# SlaveV2.net
KiCad netlist of a schematic drawn in EAGLE
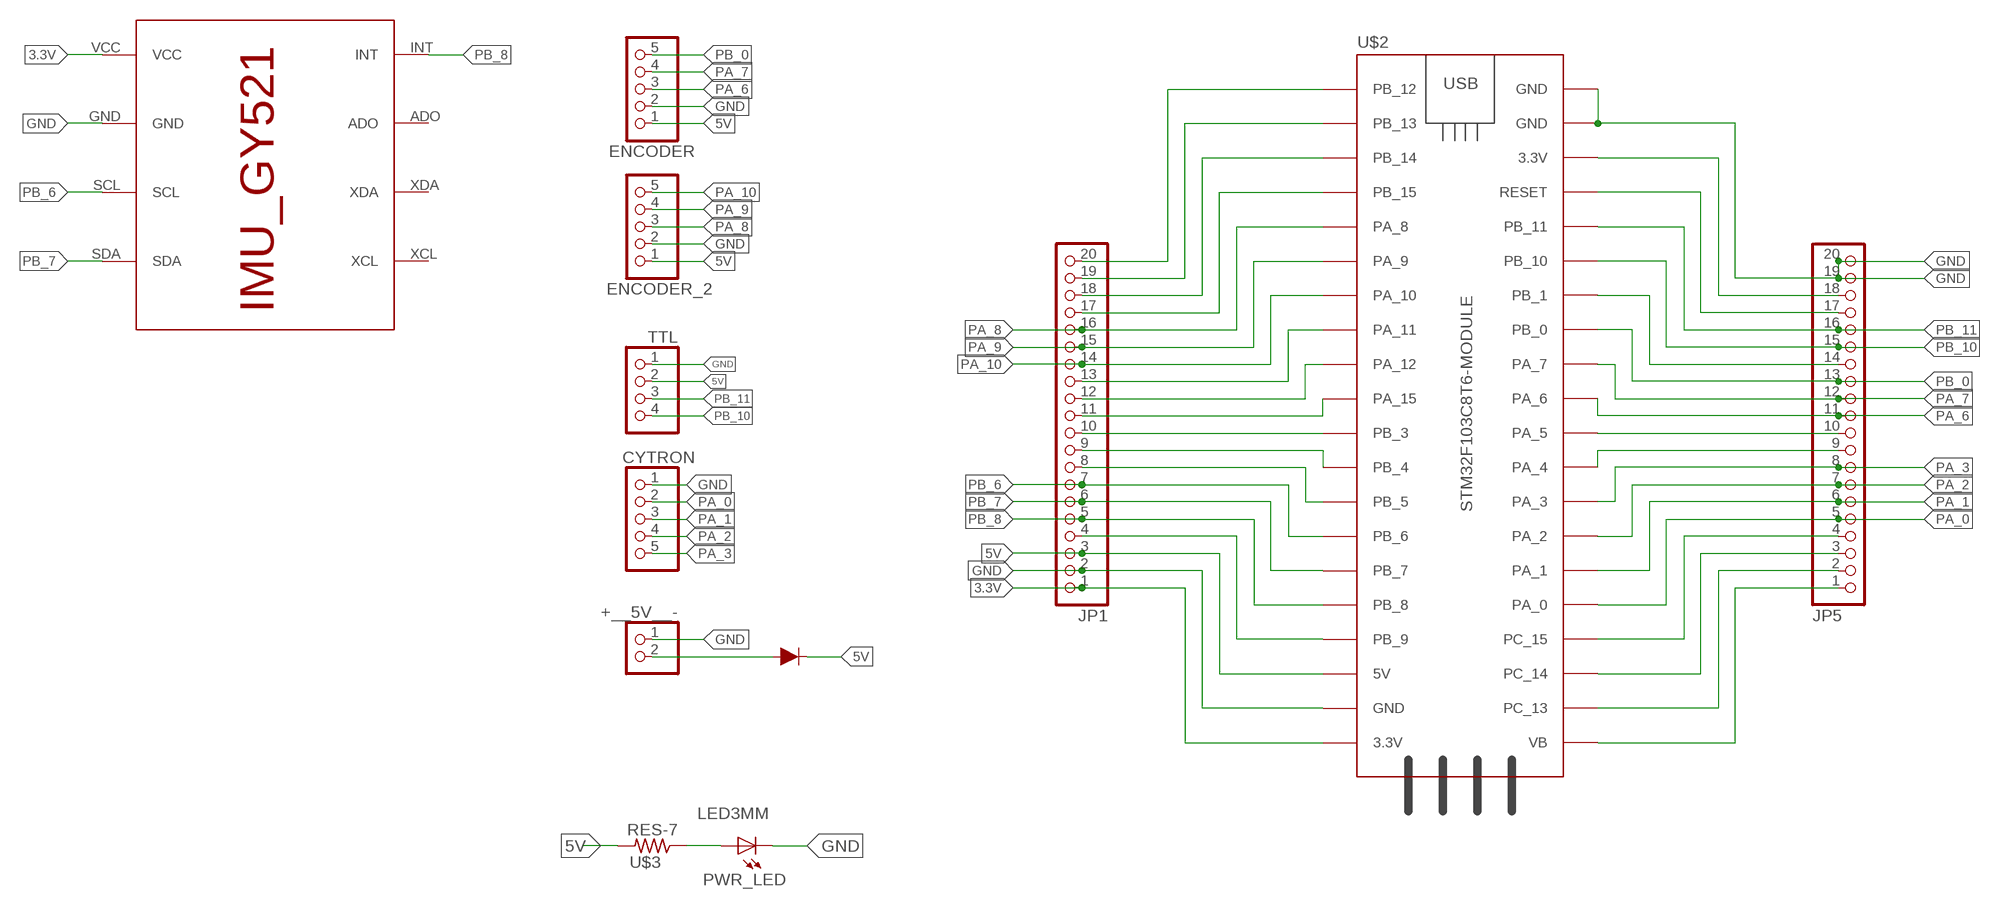
[diagram p0: schematic, sheet 1]

(export (version "E")
  (design (tool "Eeschema 10.0.6"))
  (components
    (comp (ref "+__5V__-")
      (value "PINHD-2_DATA")
      (footprint "eagle-import:1X02_DATA")
      (libsource (lib "eagle-import") (part "PINHD-2_DATA"))
    )
    (comp (ref "CYTRON")
      (value "PINHD-5_DATA")
      (footprint "eagle-import:1X05_DATA")
      (libsource (lib "eagle-import") (part "PINHD-5_DATA"))
    )
    (comp (ref "D1")
      (value "200mA/100V/1V")
      (footprint "eagle-import:DIODE-1N4148")
      (libsource (lib "eagle-import") (part "DIODE(1A)-1N4148"))
    )
    (comp (ref "ENCODER")
      (value "PINHD-5_DATA")
      (footprint "eagle-import:1X05_DATA")
      (libsource (lib "eagle-import") (part "PINHD-5_DATA"))
    )
    (comp (ref "ENCODER_2")
      (value "PINHD-5_DATA")
      (footprint "eagle-import:1X05_DATA")
      (libsource (lib "eagle-import") (part "PINHD-5_DATA"))
    )
    (comp (ref "IMU")
      (value "IMU_ROBOCON_GY521")
      (footprint "eagle-import:IMU_GY521")
      (libsource (lib "eagle-import") (part "IMU_ROBOCON_GY521"))
    )
    (comp (ref "JP1")
      (value "PINHD-1X20")
      (footprint "eagle-import:1X20")
      (libsource (lib "eagle-import") (part "PINHD-1X20"))
    )
    (comp (ref "JP5")
      (value "PINHD-1X20")
      (footprint "eagle-import:1X20")
      (libsource (lib "eagle-import") (part "PINHD-1X20"))
    )
    (comp (ref "PWR_LED")
      (value "LED3MM")
      (footprint "eagle-import:LED3MM")
      (libsource (lib "eagle-import") (part "LED3MM"))
    )
    (comp (ref "TTL")
      (value "PINHD-4_DATA")
      (footprint "eagle-import:1X04_DATA")
      (libsource (lib "eagle-import") (part "PINHD-4_DATA"))
    )
    (comp (ref "U$2")
      (value "STM32F103C8T6-MODULE")
      (footprint "eagle-import:STM32F103C8T6-MODULE")
      (libsource (lib "eagle-import") (part "STM32F103C8T6-MODULE"))
    )
    (comp (ref "U$3")
      (value "RES-7")
      (footprint "eagle-import:0204_7")
      (libsource (lib "eagle-import") (part "RES-7"))
    )
  )
  (nets
    (net (code "1") (name "3.3V") (class "Default")
      (node (ref "IMU") (pin "VCC") (pinfunction "VCC_VCC") (pintype "bidirectional"))
      (node (ref "JP1") (pin "1") (pinfunction "1_1") (pintype "passive"))
      (node (ref "U$2") (pin "3.3V_1") (pinfunction "3.3V_3.3V_1") (pintype "bidirectional"))
    )
    (net (code "2") (name "5V") (class "Default")
      (node (ref "D1") (pin "C") (pinfunction "C_C") (pintype "passive"))
      (node (ref "ENCODER") (pin "1") (pinfunction "1_1") (pintype "passive"))
      (node (ref "ENCODER_2") (pin "1") (pinfunction "1_1") (pintype "passive"))
      (node (ref "JP1") (pin "3") (pinfunction "3_3") (pintype "passive"))
      (node (ref "TTL") (pin "2") (pinfunction "2_2") (pintype "passive"))
      (node (ref "U$2") (pin "5V") (pinfunction "5V_5V") (pintype "bidirectional"))
      (node (ref "U$3") (pin "2") (pinfunction "2_2") (pintype "passive"))
    )
    (net (code "3") (name "GND") (class "Default")
      (node (ref "+__5V__-") (pin "1") (pinfunction "1_1") (pintype "passive"))
      (node (ref "CYTRON") (pin "1") (pinfunction "1_1") (pintype "passive"))
      (node (ref "ENCODER") (pin "2") (pinfunction "2_2") (pintype "passive"))
      (node (ref "ENCODER_2") (pin "2") (pinfunction "2_2") (pintype "passive"))
      (node (ref "IMU") (pin "GND") (pinfunction "GND_GND") (pintype "bidirectional"))
      (node (ref "JP1") (pin "2") (pinfunction "2_2") (pintype "passive"))
      (node (ref "JP5") (pin "19") (pinfunction "19_19") (pintype "passive"))
      (node (ref "JP5") (pin "20") (pinfunction "20_20") (pintype "passive"))
      (node (ref "PWR_LED") (pin "K") (pinfunction "C_K") (pintype "passive"))
      (node (ref "TTL") (pin "1") (pinfunction "1_1") (pintype "passive"))
      (node (ref "U$2") (pin "GND_1") (pinfunction "GND_GND_1") (pintype "bidirectional"))
      (node (ref "U$2") (pin "GND_2") (pinfunction "GND_GND_2") (pintype "bidirectional"))
      (node (ref "U$2") (pin "GND_3") (pinfunction "GND_GND_3") (pintype "power_in"))
    )
    (net (code "4") (name "Net-(+__5V__--Pad2)") (class "Default")
      (node (ref "+__5V__-") (pin "2") (pinfunction "2_2") (pintype "passive"))
      (node (ref "D1") (pin "A") (pinfunction "A_A") (pintype "passive"))
    )
    (net (code "5") (name "Net-(JP1-Pad4)") (class "Default")
      (node (ref "JP1") (pin "4") (pinfunction "4_4") (pintype "passive"))
      (node (ref "U$2") (pin "PB_9") (pinfunction "PB_9_PB_9") (pintype "bidirectional"))
    )
    (net (code "6") (name "Net-(JP1-Pad8)") (class "Default")
      (node (ref "JP1") (pin "8") (pinfunction "8_8") (pintype "passive"))
      (node (ref "U$2") (pin "PB_5") (pinfunction "PB_5_PB_5") (pintype "bidirectional"))
    )
    (net (code "7") (name "Net-(JP1-Pad9)") (class "Default")
      (node (ref "JP1") (pin "9") (pinfunction "9_9") (pintype "passive"))
      (node (ref "U$2") (pin "PB_4") (pinfunction "PB_4_PB_4") (pintype "bidirectional"))
    )
    (net (code "8") (name "Net-(JP1-Pad10)") (class "Default")
      (node (ref "JP1") (pin "10") (pinfunction "10_10") (pintype "passive"))
      (node (ref "U$2") (pin "PB_3") (pinfunction "PB_3_PB_3") (pintype "bidirectional"))
    )
    (net (code "9") (name "Net-(JP1-Pad11)") (class "Default")
      (node (ref "JP1") (pin "11") (pinfunction "11_11") (pintype "passive"))
      (node (ref "U$2") (pin "PA_15") (pinfunction "PA_15_PA_15") (pintype "bidirectional"))
    )
    (net (code "10") (name "Net-(JP1-Pad12)") (class "Default")
      (node (ref "JP1") (pin "12") (pinfunction "12_12") (pintype "passive"))
      (node (ref "U$2") (pin "PA_12") (pinfunction "PA_12_PA_12") (pintype "bidirectional"))
    )
    (net (code "11") (name "Net-(JP1-Pad13)") (class "Default")
      (node (ref "JP1") (pin "13") (pinfunction "13_13") (pintype "passive"))
      (node (ref "U$2") (pin "PA_11") (pinfunction "PA_11_PA_11") (pintype "bidirectional"))
    )
    (net (code "12") (name "Net-(JP1-Pad17)") (class "Default")
      (node (ref "JP1") (pin "17") (pinfunction "17_17") (pintype "passive"))
      (node (ref "U$2") (pin "PB_15") (pinfunction "PB_15_PB_15") (pintype "bidirectional"))
    )
    (net (code "13") (name "Net-(JP1-Pad18)") (class "Default")
      (node (ref "JP1") (pin "18") (pinfunction "18_18") (pintype "passive"))
      (node (ref "U$2") (pin "PB_14") (pinfunction "PB_14_PB_14") (pintype "bidirectional"))
    )
    (net (code "14") (name "Net-(JP1-Pad19)") (class "Default")
      (node (ref "JP1") (pin "19") (pinfunction "19_19") (pintype "passive"))
      (node (ref "U$2") (pin "PB_13") (pinfunction "PB_13_PB_13") (pintype "bidirectional"))
    )
    (net (code "15") (name "Net-(JP1-Pad20)") (class "Default")
      (node (ref "JP1") (pin "20") (pinfunction "20_20") (pintype "passive"))
      (node (ref "U$2") (pin "PB_12") (pinfunction "PB_12_PB_12") (pintype "bidirectional"))
    )
    (net (code "16") (name "Net-(JP5-Pad1)") (class "Default")
      (node (ref "JP5") (pin "1") (pinfunction "1_1") (pintype "passive"))
      (node (ref "U$2") (pin "VB") (pinfunction "VB_VB") (pintype "bidirectional"))
    )
    (net (code "17") (name "Net-(JP5-Pad2)") (class "Default")
      (node (ref "JP5") (pin "2") (pinfunction "2_2") (pintype "passive"))
      (node (ref "U$2") (pin "PC_13") (pinfunction "PC_13_PC_13") (pintype "bidirectional"))
    )
    (net (code "18") (name "Net-(JP5-Pad3)") (class "Default")
      (node (ref "JP5") (pin "3") (pinfunction "3_3") (pintype "passive"))
      (node (ref "U$2") (pin "PC_14") (pinfunction "PC_14_PC_14") (pintype "bidirectional"))
    )
    (net (code "19") (name "Net-(JP5-Pad4)") (class "Default")
      (node (ref "JP5") (pin "4") (pinfunction "4_4") (pintype "passive"))
      (node (ref "U$2") (pin "PC_15") (pinfunction "PC_15_PC_15") (pintype "bidirectional"))
    )
    (net (code "20") (name "Net-(JP5-Pad9)") (class "Default")
      (node (ref "JP5") (pin "9") (pinfunction "9_9") (pintype "passive"))
      (node (ref "U$2") (pin "PA_4") (pinfunction "PA_4_PA_4") (pintype "bidirectional"))
    )
    (net (code "21") (name "Net-(JP5-Pad10)") (class "Default")
      (node (ref "JP5") (pin "10") (pinfunction "10_10") (pintype "passive"))
      (node (ref "U$2") (pin "PA_5") (pinfunction "PA_5_PA_5") (pintype "bidirectional"))
    )
    (net (code "22") (name "Net-(JP5-Pad14)") (class "Default")
      (node (ref "JP5") (pin "14") (pinfunction "14_14") (pintype "passive"))
      (node (ref "U$2") (pin "PB_1") (pinfunction "PB_1_PB_1") (pintype "bidirectional"))
    )
    (net (code "23") (name "Net-(JP5-Pad17)") (class "Default")
      (node (ref "JP5") (pin "17") (pinfunction "17_17") (pintype "passive"))
      (node (ref "U$2") (pin "RESET") (pinfunction "RESET_RESET") (pintype "bidirectional"))
    )
    (net (code "24") (name "Net-(JP5-Pad18)") (class "Default")
      (node (ref "JP5") (pin "18") (pinfunction "18_18") (pintype "passive"))
      (node (ref "U$2") (pin "3.3V_2") (pinfunction "3.3V_3.3V_2") (pintype "bidirectional"))
    )
    (net (code "25") (name "Net-(PWR_LED-PadA)") (class "Default")
      (node (ref "PWR_LED") (pin "A") (pinfunction "A_A") (pintype "passive"))
      (node (ref "U$3") (pin "1") (pinfunction "1_1") (pintype "passive"))
    )
    (net (code "26") (name "PA_0") (class "Default")
      (node (ref "CYTRON") (pin "2") (pinfunction "2_2") (pintype "passive"))
      (node (ref "JP5") (pin "5") (pinfunction "5_5") (pintype "passive"))
      (node (ref "U$2") (pin "PA_0") (pinfunction "PA_0_PA_0") (pintype "bidirectional"))
    )
    (net (code "27") (name "PA_1") (class "Default")
      (node (ref "CYTRON") (pin "3") (pinfunction "3_3") (pintype "passive"))
      (node (ref "JP5") (pin "6") (pinfunction "6_6") (pintype "passive"))
      (node (ref "U$2") (pin "PA_1") (pinfunction "PA_1_PA_1") (pintype "bidirectional"))
    )
    (net (code "28") (name "PA_2") (class "Default")
      (node (ref "CYTRON") (pin "4") (pinfunction "4_4") (pintype "passive"))
      (node (ref "JP5") (pin "7") (pinfunction "7_7") (pintype "passive"))
      (node (ref "U$2") (pin "PA_2") (pinfunction "PA_2_PA_2") (pintype "bidirectional"))
    )
    (net (code "29") (name "PA_3") (class "Default")
      (node (ref "CYTRON") (pin "5") (pinfunction "5_5") (pintype "passive"))
      (node (ref "JP5") (pin "8") (pinfunction "8_8") (pintype "passive"))
      (node (ref "U$2") (pin "PA_3") (pinfunction "PA_3_PA_3") (pintype "bidirectional"))
    )
    (net (code "30") (name "PA_6") (class "Default")
      (node (ref "ENCODER") (pin "3") (pinfunction "3_3") (pintype "passive"))
      (node (ref "JP5") (pin "11") (pinfunction "11_11") (pintype "passive"))
      (node (ref "U$2") (pin "PA_6") (pinfunction "PA_6_PA_6") (pintype "bidirectional"))
    )
    (net (code "31") (name "PA_7") (class "Default")
      (node (ref "ENCODER") (pin "4") (pinfunction "4_4") (pintype "passive"))
      (node (ref "JP5") (pin "12") (pinfunction "12_12") (pintype "passive"))
      (node (ref "U$2") (pin "PA_7") (pinfunction "PA_7_PA_7") (pintype "bidirectional"))
    )
    (net (code "32") (name "PA_8") (class "Default")
      (node (ref "ENCODER_2") (pin "3") (pinfunction "3_3") (pintype "passive"))
      (node (ref "JP1") (pin "16") (pinfunction "16_16") (pintype "passive"))
      (node (ref "U$2") (pin "PA_8") (pinfunction "PA_8_PA_8") (pintype "bidirectional"))
    )
    (net (code "33") (name "PA_9") (class "Default")
      (node (ref "ENCODER_2") (pin "4") (pinfunction "4_4") (pintype "passive"))
      (node (ref "JP1") (pin "15") (pinfunction "15_15") (pintype "passive"))
      (node (ref "U$2") (pin "PA_9") (pinfunction "PA_9_PA_9") (pintype "bidirectional"))
    )
    (net (code "34") (name "PA_10") (class "Default")
      (node (ref "ENCODER_2") (pin "5") (pinfunction "5_5") (pintype "passive"))
      (node (ref "JP1") (pin "14") (pinfunction "14_14") (pintype "passive"))
      (node (ref "U$2") (pin "PA_10") (pinfunction "PA_10_PA_10") (pintype "bidirectional"))
    )
    (net (code "35") (name "PB_0") (class "Default")
      (node (ref "ENCODER") (pin "5") (pinfunction "5_5") (pintype "passive"))
      (node (ref "JP5") (pin "13") (pinfunction "13_13") (pintype "passive"))
      (node (ref "U$2") (pin "PB_0") (pinfunction "PB_0_PB_0") (pintype "bidirectional"))
    )
    (net (code "36") (name "PB_6") (class "Default")
      (node (ref "IMU") (pin "SCL") (pinfunction "SCL_SCL") (pintype "bidirectional"))
      (node (ref "JP1") (pin "7") (pinfunction "7_7") (pintype "passive"))
      (node (ref "U$2") (pin "PB_6") (pinfunction "PB_6_PB_6") (pintype "bidirectional"))
    )
    (net (code "37") (name "PB_7") (class "Default")
      (node (ref "IMU") (pin "SDA") (pinfunction "SDA_SDA") (pintype "bidirectional"))
      (node (ref "JP1") (pin "6") (pinfunction "6_6") (pintype "passive"))
      (node (ref "U$2") (pin "PB_7") (pinfunction "PB_7_PB_7") (pintype "bidirectional"))
    )
    (net (code "38") (name "PB_8") (class "Default")
      (node (ref "IMU") (pin "INT") (pinfunction "INT_INT") (pintype "bidirectional"))
      (node (ref "JP1") (pin "5") (pinfunction "5_5") (pintype "passive"))
      (node (ref "U$2") (pin "PB_8") (pinfunction "PB_8_PB_8") (pintype "bidirectional"))
    )
    (net (code "39") (name "PB_10") (class "Default")
      (node (ref "JP5") (pin "15") (pinfunction "15_15") (pintype "passive"))
      (node (ref "TTL") (pin "4") (pinfunction "4_4") (pintype "passive"))
      (node (ref "U$2") (pin "PB_10") (pinfunction "PB_10_PB_10") (pintype "bidirectional"))
    )
    (net (code "40") (name "PB_11") (class "Default")
      (node (ref "JP5") (pin "16") (pinfunction "16_16") (pintype "passive"))
      (node (ref "TTL") (pin "3") (pinfunction "3_3") (pintype "passive"))
      (node (ref "U$2") (pin "PB_11") (pinfunction "PB_11_PB_11") (pintype "bidirectional"))
    )
    (net (code "41") (name "unconnected-(IMU-PadADO)") (class "Default")
      (node (ref "IMU") (pin "ADO") (pinfunction "ADO_ADO") (pintype "bidirectional"))
    )
    (net (code "42") (name "unconnected-(IMU-PadXCL)") (class "Default")
      (node (ref "IMU") (pin "XCL") (pinfunction "XCL_XCL") (pintype "bidirectional"))
    )
    (net (code "43") (name "unconnected-(IMU-PadXDA)") (class "Default")
      (node (ref "IMU") (pin "XDA") (pinfunction "XDA_XDA") (pintype "bidirectional"))
    )
  )
)
